# Raspberry_Pi_2_Breakout.net
KiCad netlist of a schematic drawn in EAGLE
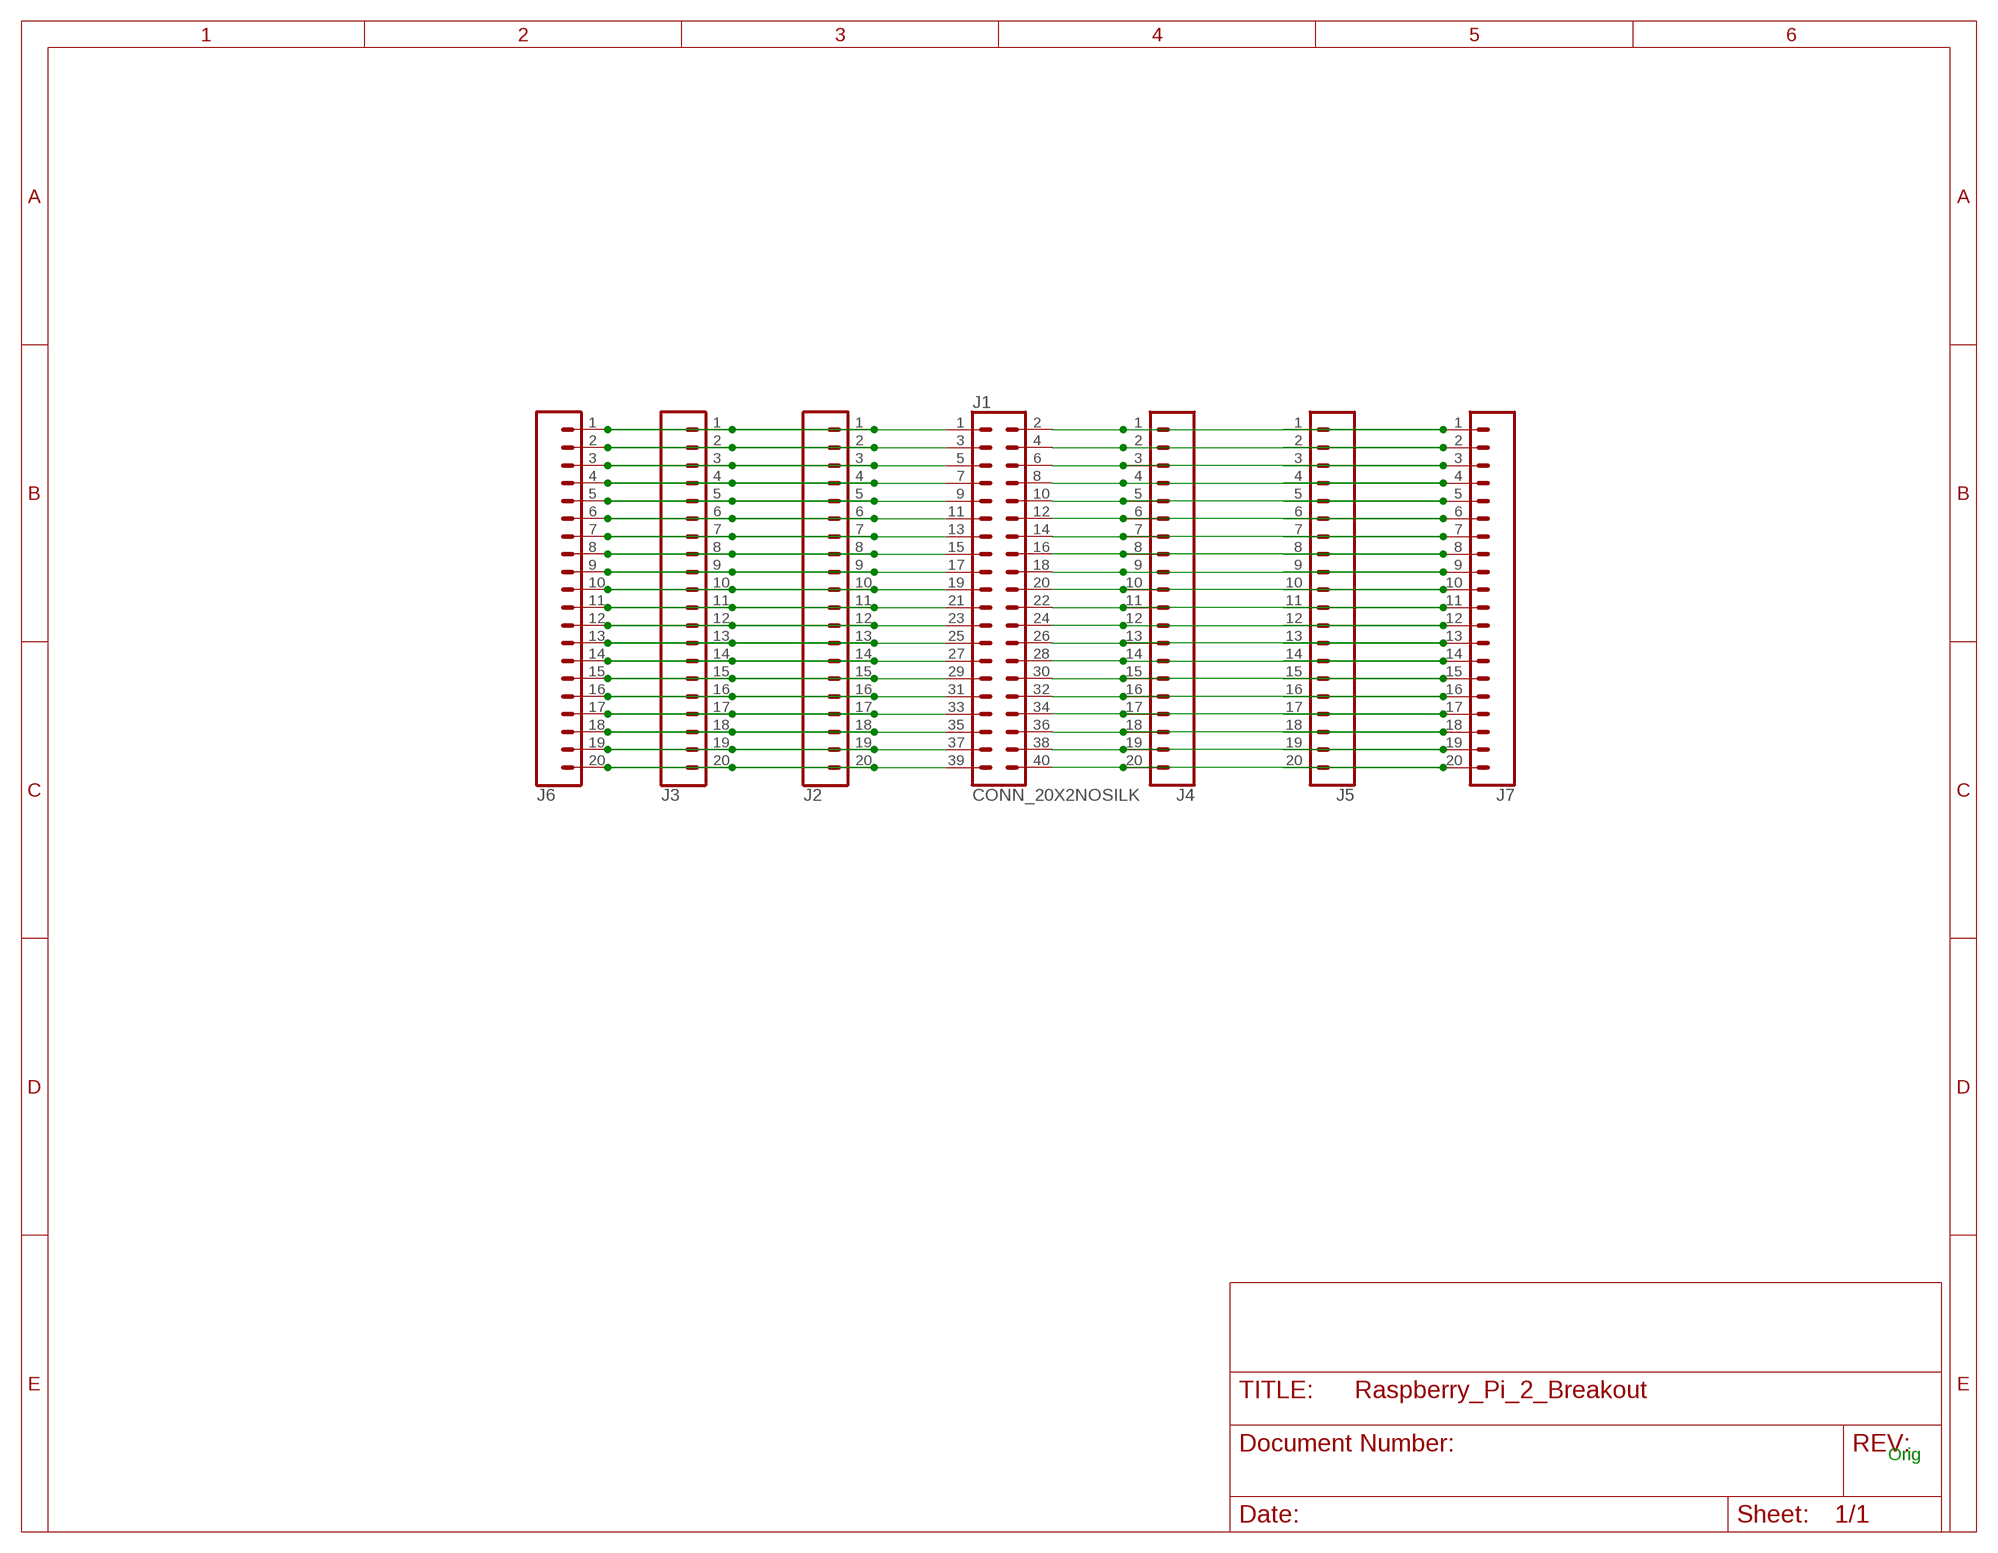
[diagram p0: schematic, sheet 1]

(export (version "E")
  (design (tool "Eeschema 10.0.6"))
  (components
    (comp (ref "J1")
      (value "CONN_20X2NOSILK")
      (footprint "eagle-import:2X20_NOSILK")
      (libsource (lib "eagle-import") (part "CONN_20X2NOSILK"))
    )
    (comp (ref "J2")
      (value "CONN_20NOSILK")
      (footprint "eagle-import:1X20_NOSILK")
      (libsource (lib "eagle-import") (part "CONN_20NOSILK"))
    )
    (comp (ref "J3")
      (value "CONN_20NOSILK")
      (footprint "eagle-import:1X20_NOSILK")
      (libsource (lib "eagle-import") (part "CONN_20NOSILK"))
    )
    (comp (ref "J4")
      (value "CONN_20NOSILK")
      (footprint "eagle-import:1X20_NOSILK")
      (libsource (lib "eagle-import") (part "CONN_20NOSILK"))
    )
    (comp (ref "J5")
      (value "CONN_20NOSILK")
      (footprint "eagle-import:1X20_NOSILK")
      (libsource (lib "eagle-import") (part "CONN_20NOSILK"))
    )
    (comp (ref "J6")
      (value "CONN_20NOSILK")
      (footprint "eagle-import:1X20_NOSILK")
      (libsource (lib "eagle-import") (part "CONN_20NOSILK"))
    )
    (comp (ref "J7")
      (value "CONN_20NOSILK")
      (footprint "eagle-import:1X20_NOSILK")
      (libsource (lib "eagle-import") (part "CONN_20NOSILK"))
    )
  )
  (nets
    (net (code "1") (name "Net-(J1-Pad1)") (class "Default")
      (node (ref "J1") (pin "1") (pinfunction "1_1") (pintype "passive"))
      (node (ref "J2") (pin "1") (pinfunction "1_1") (pintype "passive"))
      (node (ref "J3") (pin "1") (pinfunction "1_1") (pintype "passive"))
      (node (ref "J6") (pin "1") (pinfunction "1_1") (pintype "passive"))
    )
    (net (code "2") (name "Net-(J1-Pad2)") (class "Default")
      (node (ref "J1") (pin "2") (pinfunction "2_2") (pintype "passive"))
      (node (ref "J4") (pin "1") (pinfunction "1_1") (pintype "passive"))
      (node (ref "J5") (pin "1") (pinfunction "1_1") (pintype "passive"))
      (node (ref "J7") (pin "1") (pinfunction "1_1") (pintype "passive"))
    )
    (net (code "3") (name "Net-(J1-Pad3)") (class "Default")
      (node (ref "J1") (pin "3") (pinfunction "3_3") (pintype "passive"))
      (node (ref "J2") (pin "2") (pinfunction "2_2") (pintype "passive"))
      (node (ref "J3") (pin "2") (pinfunction "2_2") (pintype "passive"))
      (node (ref "J6") (pin "2") (pinfunction "2_2") (pintype "passive"))
    )
    (net (code "4") (name "Net-(J1-Pad4)") (class "Default")
      (node (ref "J1") (pin "4") (pinfunction "4_4") (pintype "passive"))
      (node (ref "J4") (pin "2") (pinfunction "2_2") (pintype "passive"))
      (node (ref "J5") (pin "2") (pinfunction "2_2") (pintype "passive"))
      (node (ref "J7") (pin "2") (pinfunction "2_2") (pintype "passive"))
    )
    (net (code "5") (name "Net-(J1-Pad5)") (class "Default")
      (node (ref "J1") (pin "5") (pinfunction "5_5") (pintype "passive"))
      (node (ref "J2") (pin "3") (pinfunction "3_3") (pintype "passive"))
      (node (ref "J3") (pin "3") (pinfunction "3_3") (pintype "passive"))
      (node (ref "J6") (pin "3") (pinfunction "3_3") (pintype "passive"))
    )
    (net (code "6") (name "Net-(J1-Pad6)") (class "Default")
      (node (ref "J1") (pin "6") (pinfunction "6_6") (pintype "passive"))
      (node (ref "J4") (pin "3") (pinfunction "3_3") (pintype "passive"))
      (node (ref "J5") (pin "3") (pinfunction "3_3") (pintype "passive"))
      (node (ref "J7") (pin "3") (pinfunction "3_3") (pintype "passive"))
    )
    (net (code "7") (name "Net-(J1-Pad7)") (class "Default")
      (node (ref "J1") (pin "7") (pinfunction "7_7") (pintype "passive"))
      (node (ref "J2") (pin "4") (pinfunction "4_4") (pintype "passive"))
      (node (ref "J3") (pin "4") (pinfunction "4_4") (pintype "passive"))
      (node (ref "J6") (pin "4") (pinfunction "4_4") (pintype "passive"))
    )
    (net (code "8") (name "Net-(J1-Pad8)") (class "Default")
      (node (ref "J1") (pin "8") (pinfunction "8_8") (pintype "passive"))
      (node (ref "J4") (pin "4") (pinfunction "4_4") (pintype "passive"))
      (node (ref "J5") (pin "4") (pinfunction "4_4") (pintype "passive"))
      (node (ref "J7") (pin "4") (pinfunction "4_4") (pintype "passive"))
    )
    (net (code "9") (name "Net-(J1-Pad9)") (class "Default")
      (node (ref "J1") (pin "9") (pinfunction "9_9") (pintype "passive"))
      (node (ref "J2") (pin "5") (pinfunction "5_5") (pintype "passive"))
      (node (ref "J3") (pin "5") (pinfunction "5_5") (pintype "passive"))
      (node (ref "J6") (pin "5") (pinfunction "5_5") (pintype "passive"))
    )
    (net (code "10") (name "Net-(J1-Pad10)") (class "Default")
      (node (ref "J1") (pin "10") (pinfunction "10_10") (pintype "passive"))
      (node (ref "J4") (pin "5") (pinfunction "5_5") (pintype "passive"))
      (node (ref "J5") (pin "5") (pinfunction "5_5") (pintype "passive"))
      (node (ref "J7") (pin "5") (pinfunction "5_5") (pintype "passive"))
    )
    (net (code "11") (name "Net-(J1-Pad11)") (class "Default")
      (node (ref "J1") (pin "11") (pinfunction "11_11") (pintype "passive"))
      (node (ref "J2") (pin "6") (pinfunction "6_6") (pintype "passive"))
      (node (ref "J3") (pin "6") (pinfunction "6_6") (pintype "passive"))
      (node (ref "J6") (pin "6") (pinfunction "6_6") (pintype "passive"))
    )
    (net (code "12") (name "Net-(J1-Pad12)") (class "Default")
      (node (ref "J1") (pin "12") (pinfunction "12_12") (pintype "passive"))
      (node (ref "J4") (pin "6") (pinfunction "6_6") (pintype "passive"))
      (node (ref "J5") (pin "6") (pinfunction "6_6") (pintype "passive"))
      (node (ref "J7") (pin "6") (pinfunction "6_6") (pintype "passive"))
    )
    (net (code "13") (name "Net-(J1-Pad13)") (class "Default")
      (node (ref "J1") (pin "13") (pinfunction "13_13") (pintype "passive"))
      (node (ref "J2") (pin "7") (pinfunction "7_7") (pintype "passive"))
      (node (ref "J3") (pin "7") (pinfunction "7_7") (pintype "passive"))
      (node (ref "J6") (pin "7") (pinfunction "7_7") (pintype "passive"))
    )
    (net (code "14") (name "Net-(J1-Pad14)") (class "Default")
      (node (ref "J1") (pin "14") (pinfunction "14_14") (pintype "passive"))
      (node (ref "J4") (pin "7") (pinfunction "7_7") (pintype "passive"))
      (node (ref "J5") (pin "7") (pinfunction "7_7") (pintype "passive"))
      (node (ref "J7") (pin "7") (pinfunction "7_7") (pintype "passive"))
    )
    (net (code "15") (name "Net-(J1-Pad15)") (class "Default")
      (node (ref "J1") (pin "15") (pinfunction "15_15") (pintype "passive"))
      (node (ref "J2") (pin "8") (pinfunction "8_8") (pintype "passive"))
      (node (ref "J3") (pin "8") (pinfunction "8_8") (pintype "passive"))
      (node (ref "J6") (pin "8") (pinfunction "8_8") (pintype "passive"))
    )
    (net (code "16") (name "Net-(J1-Pad16)") (class "Default")
      (node (ref "J1") (pin "16") (pinfunction "16_16") (pintype "passive"))
      (node (ref "J4") (pin "8") (pinfunction "8_8") (pintype "passive"))
      (node (ref "J5") (pin "8") (pinfunction "8_8") (pintype "passive"))
      (node (ref "J7") (pin "8") (pinfunction "8_8") (pintype "passive"))
    )
    (net (code "17") (name "Net-(J1-Pad17)") (class "Default")
      (node (ref "J1") (pin "17") (pinfunction "17_17") (pintype "passive"))
      (node (ref "J2") (pin "9") (pinfunction "9_9") (pintype "passive"))
      (node (ref "J3") (pin "9") (pinfunction "9_9") (pintype "passive"))
      (node (ref "J6") (pin "9") (pinfunction "9_9") (pintype "passive"))
    )
    (net (code "18") (name "Net-(J1-Pad18)") (class "Default")
      (node (ref "J1") (pin "18") (pinfunction "18_18") (pintype "passive"))
      (node (ref "J4") (pin "9") (pinfunction "9_9") (pintype "passive"))
      (node (ref "J5") (pin "9") (pinfunction "9_9") (pintype "passive"))
      (node (ref "J7") (pin "9") (pinfunction "9_9") (pintype "passive"))
    )
    (net (code "19") (name "Net-(J1-Pad19)") (class "Default")
      (node (ref "J1") (pin "19") (pinfunction "19_19") (pintype "passive"))
      (node (ref "J2") (pin "10") (pinfunction "10_10") (pintype "passive"))
      (node (ref "J3") (pin "10") (pinfunction "10_10") (pintype "passive"))
      (node (ref "J6") (pin "10") (pinfunction "10_10") (pintype "passive"))
    )
    (net (code "20") (name "Net-(J1-Pad20)") (class "Default")
      (node (ref "J1") (pin "20") (pinfunction "20_20") (pintype "passive"))
      (node (ref "J4") (pin "10") (pinfunction "10_10") (pintype "passive"))
      (node (ref "J5") (pin "10") (pinfunction "10_10") (pintype "passive"))
      (node (ref "J7") (pin "10") (pinfunction "10_10") (pintype "passive"))
    )
    (net (code "21") (name "Net-(J1-Pad21)") (class "Default")
      (node (ref "J1") (pin "21") (pinfunction "21_21") (pintype "passive"))
      (node (ref "J2") (pin "11") (pinfunction "11_11") (pintype "passive"))
      (node (ref "J3") (pin "11") (pinfunction "11_11") (pintype "passive"))
      (node (ref "J6") (pin "11") (pinfunction "11_11") (pintype "passive"))
    )
    (net (code "22") (name "Net-(J1-Pad22)") (class "Default")
      (node (ref "J1") (pin "22") (pinfunction "22_22") (pintype "passive"))
      (node (ref "J4") (pin "11") (pinfunction "11_11") (pintype "passive"))
      (node (ref "J5") (pin "11") (pinfunction "11_11") (pintype "passive"))
      (node (ref "J7") (pin "11") (pinfunction "11_11") (pintype "passive"))
    )
    (net (code "23") (name "Net-(J1-Pad23)") (class "Default")
      (node (ref "J1") (pin "23") (pinfunction "23_23") (pintype "passive"))
      (node (ref "J2") (pin "12") (pinfunction "12_12") (pintype "passive"))
      (node (ref "J3") (pin "12") (pinfunction "12_12") (pintype "passive"))
      (node (ref "J6") (pin "12") (pinfunction "12_12") (pintype "passive"))
    )
    (net (code "24") (name "Net-(J1-Pad24)") (class "Default")
      (node (ref "J1") (pin "24") (pinfunction "24_24") (pintype "passive"))
      (node (ref "J4") (pin "12") (pinfunction "12_12") (pintype "passive"))
      (node (ref "J5") (pin "12") (pinfunction "12_12") (pintype "passive"))
      (node (ref "J7") (pin "12") (pinfunction "12_12") (pintype "passive"))
    )
    (net (code "25") (name "Net-(J1-Pad25)") (class "Default")
      (node (ref "J1") (pin "25") (pinfunction "25_25") (pintype "passive"))
      (node (ref "J2") (pin "13") (pinfunction "13_13") (pintype "passive"))
      (node (ref "J3") (pin "13") (pinfunction "13_13") (pintype "passive"))
      (node (ref "J6") (pin "13") (pinfunction "13_13") (pintype "passive"))
    )
    (net (code "26") (name "Net-(J1-Pad26)") (class "Default")
      (node (ref "J1") (pin "26") (pinfunction "26_26") (pintype "passive"))
      (node (ref "J4") (pin "13") (pinfunction "13_13") (pintype "passive"))
      (node (ref "J5") (pin "13") (pinfunction "13_13") (pintype "passive"))
      (node (ref "J7") (pin "13") (pinfunction "13_13") (pintype "passive"))
    )
    (net (code "27") (name "Net-(J1-Pad27)") (class "Default")
      (node (ref "J1") (pin "27") (pinfunction "27_27") (pintype "passive"))
      (node (ref "J2") (pin "14") (pinfunction "14_14") (pintype "passive"))
      (node (ref "J3") (pin "14") (pinfunction "14_14") (pintype "passive"))
      (node (ref "J6") (pin "14") (pinfunction "14_14") (pintype "passive"))
    )
    (net (code "28") (name "Net-(J1-Pad28)") (class "Default")
      (node (ref "J1") (pin "28") (pinfunction "28_28") (pintype "passive"))
      (node (ref "J4") (pin "14") (pinfunction "14_14") (pintype "passive"))
      (node (ref "J5") (pin "14") (pinfunction "14_14") (pintype "passive"))
      (node (ref "J7") (pin "14") (pinfunction "14_14") (pintype "passive"))
    )
    (net (code "29") (name "Net-(J1-Pad29)") (class "Default")
      (node (ref "J1") (pin "29") (pinfunction "29_29") (pintype "passive"))
      (node (ref "J2") (pin "15") (pinfunction "15_15") (pintype "passive"))
      (node (ref "J3") (pin "15") (pinfunction "15_15") (pintype "passive"))
      (node (ref "J6") (pin "15") (pinfunction "15_15") (pintype "passive"))
    )
    (net (code "30") (name "Net-(J1-Pad30)") (class "Default")
      (node (ref "J1") (pin "30") (pinfunction "30_30") (pintype "passive"))
      (node (ref "J4") (pin "15") (pinfunction "15_15") (pintype "passive"))
      (node (ref "J5") (pin "15") (pinfunction "15_15") (pintype "passive"))
      (node (ref "J7") (pin "15") (pinfunction "15_15") (pintype "passive"))
    )
    (net (code "31") (name "Net-(J1-Pad31)") (class "Default")
      (node (ref "J1") (pin "31") (pinfunction "31_31") (pintype "passive"))
      (node (ref "J2") (pin "16") (pinfunction "16_16") (pintype "passive"))
      (node (ref "J3") (pin "16") (pinfunction "16_16") (pintype "passive"))
      (node (ref "J6") (pin "16") (pinfunction "16_16") (pintype "passive"))
    )
    (net (code "32") (name "Net-(J1-Pad32)") (class "Default")
      (node (ref "J1") (pin "32") (pinfunction "32_32") (pintype "passive"))
      (node (ref "J4") (pin "16") (pinfunction "16_16") (pintype "passive"))
      (node (ref "J5") (pin "16") (pinfunction "16_16") (pintype "passive"))
      (node (ref "J7") (pin "16") (pinfunction "16_16") (pintype "passive"))
    )
    (net (code "33") (name "Net-(J1-Pad33)") (class "Default")
      (node (ref "J1") (pin "33") (pinfunction "33_33") (pintype "passive"))
      (node (ref "J2") (pin "17") (pinfunction "17_17") (pintype "passive"))
      (node (ref "J3") (pin "17") (pinfunction "17_17") (pintype "passive"))
      (node (ref "J6") (pin "17") (pinfunction "17_17") (pintype "passive"))
    )
    (net (code "34") (name "Net-(J1-Pad34)") (class "Default")
      (node (ref "J1") (pin "34") (pinfunction "34_34") (pintype "passive"))
      (node (ref "J4") (pin "17") (pinfunction "17_17") (pintype "passive"))
      (node (ref "J5") (pin "17") (pinfunction "17_17") (pintype "passive"))
      (node (ref "J7") (pin "17") (pinfunction "17_17") (pintype "passive"))
    )
    (net (code "35") (name "Net-(J1-Pad35)") (class "Default")
      (node (ref "J1") (pin "35") (pinfunction "35_35") (pintype "passive"))
      (node (ref "J2") (pin "18") (pinfunction "18_18") (pintype "passive"))
      (node (ref "J3") (pin "18") (pinfunction "18_18") (pintype "passive"))
      (node (ref "J6") (pin "18") (pinfunction "18_18") (pintype "passive"))
    )
    (net (code "36") (name "Net-(J1-Pad36)") (class "Default")
      (node (ref "J1") (pin "36") (pinfunction "36_36") (pintype "passive"))
      (node (ref "J4") (pin "18") (pinfunction "18_18") (pintype "passive"))
      (node (ref "J5") (pin "18") (pinfunction "18_18") (pintype "passive"))
      (node (ref "J7") (pin "18") (pinfunction "18_18") (pintype "passive"))
    )
    (net (code "37") (name "Net-(J1-Pad37)") (class "Default")
      (node (ref "J1") (pin "37") (pinfunction "37_37") (pintype "passive"))
      (node (ref "J2") (pin "19") (pinfunction "19_19") (pintype "passive"))
      (node (ref "J3") (pin "19") (pinfunction "19_19") (pintype "passive"))
      (node (ref "J6") (pin "19") (pinfunction "19_19") (pintype "passive"))
    )
    (net (code "38") (name "Net-(J1-Pad38)") (class "Default")
      (node (ref "J1") (pin "38") (pinfunction "38_38") (pintype "passive"))
      (node (ref "J4") (pin "19") (pinfunction "19_19") (pintype "passive"))
      (node (ref "J5") (pin "19") (pinfunction "19_19") (pintype "passive"))
      (node (ref "J7") (pin "19") (pinfunction "19_19") (pintype "passive"))
    )
    (net (code "39") (name "Net-(J1-Pad39)") (class "Default")
      (node (ref "J1") (pin "39") (pinfunction "39_39") (pintype "passive"))
      (node (ref "J2") (pin "20") (pinfunction "20_20") (pintype "passive"))
      (node (ref "J3") (pin "20") (pinfunction "20_20") (pintype "passive"))
      (node (ref "J6") (pin "20") (pinfunction "20_20") (pintype "passive"))
    )
    (net (code "40") (name "Net-(J1-Pad40)") (class "Default")
      (node (ref "J1") (pin "40") (pinfunction "40_40") (pintype "passive"))
      (node (ref "J4") (pin "20") (pinfunction "20_20") (pintype "passive"))
      (node (ref "J5") (pin "20") (pinfunction "20_20") (pintype "passive"))
      (node (ref "J7") (pin "20") (pinfunction "20_20") (pintype "passive"))
    )
  )
)
